# sheet1.net
KiCad netlist of a schematic drawn in Altium Designer
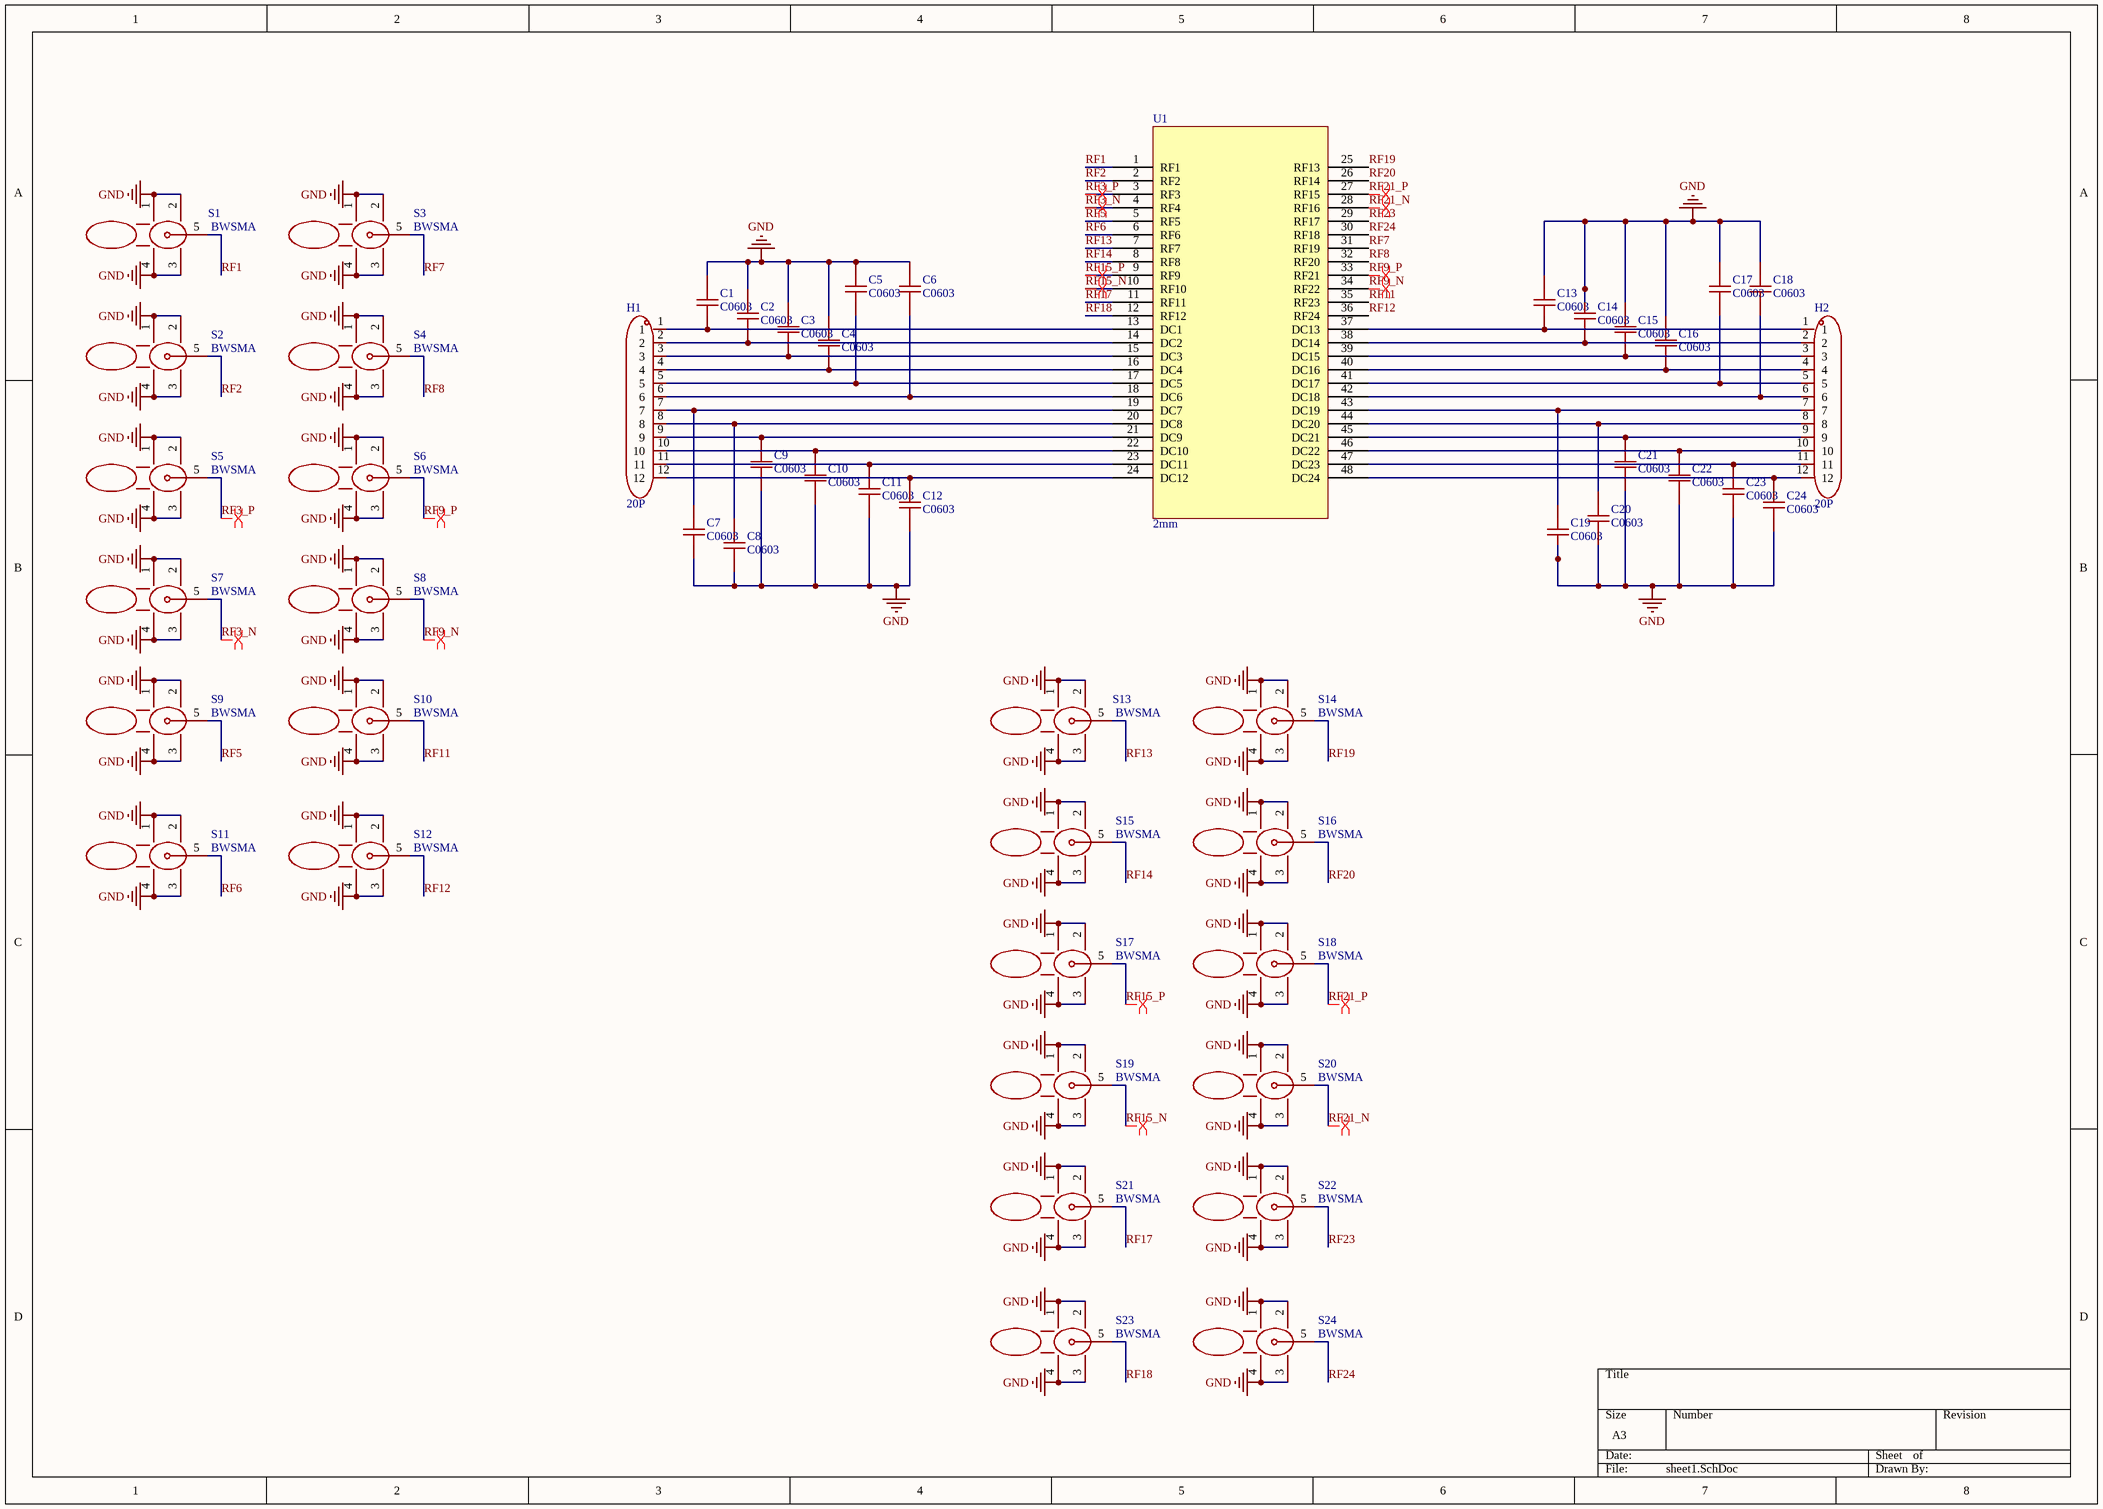
[diagram p0: sheet1.SchDoc]

(export (version "E")
  (design (tool "Eeschema 10.0.6"))
  (components
    (comp (ref "C1") (value "C0603") (footprint "C0603") (libsource (lib "Cap") (part "C0603")))
    (comp (ref "C2") (value "C0603") (footprint "C0603") (libsource (lib "Cap") (part "C0603")))
    (comp (ref "C3") (value "C0603") (footprint "C0603") (libsource (lib "Cap") (part "C0603")))
    (comp (ref "C4") (value "C0603") (footprint "C0603") (libsource (lib "Cap") (part "C0603")))
    (comp (ref "C5") (value "C0603") (footprint "C0603") (libsource (lib "Cap") (part "C0603")))
    (comp (ref "C6") (value "C0603") (footprint "C0603") (libsource (lib "Cap") (part "C0603")))
    (comp (ref "C7") (value "C0603") (footprint "C0603") (libsource (lib "Cap") (part "C0603")))
    (comp (ref "C8") (value "C0603") (footprint "C0603") (libsource (lib "Cap") (part "C0603")))
    (comp (ref "C9") (value "C0603") (footprint "C0603") (libsource (lib "Cap") (part "C0603")))
    (comp (ref "C10") (value "C0603") (footprint "C0603") (libsource (lib "Cap") (part "C0603")))
    (comp (ref "C11") (value "C0603") (footprint "C0603") (libsource (lib "Cap") (part "C0603")))
    (comp (ref "C12") (value "C0603") (footprint "C0603") (libsource (lib "Cap") (part "C0603")))
    (comp (ref "C13") (value "C0603") (footprint "C0603") (libsource (lib "Cap") (part "C0603")))
    (comp (ref "C14") (value "C0603") (footprint "C0603") (libsource (lib "Cap") (part "C0603")))
    (comp (ref "C15") (value "C0603") (footprint "C0603") (libsource (lib "Cap") (part "C0603")))
    (comp (ref "C16") (value "C0603") (footprint "C0603") (libsource (lib "Cap") (part "C0603")))
    (comp (ref "C17") (value "C0603") (footprint "C0603") (libsource (lib "Cap") (part "C0603")))
    (comp (ref "C18") (value "C0603") (footprint "C0603") (libsource (lib "Cap") (part "C0603")))
    (comp (ref "C19") (value "C0603") (footprint "C0603") (libsource (lib "Cap") (part "C0603")))
    (comp (ref "C20") (value "C0603") (footprint "C0603") (libsource (lib "Cap") (part "C0603")))
    (comp (ref "C21") (value "C0603") (footprint "C0603") (libsource (lib "Cap") (part "C0603")))
    (comp (ref "C22") (value "C0603") (footprint "C0603") (libsource (lib "Cap") (part "C0603")))
    (comp (ref "C23") (value "C0603") (footprint "C0603") (libsource (lib "Cap") (part "C0603")))
    (comp (ref "C24") (value "C0603") (footprint "C0603") (libsource (lib "Cap") (part "C0603")))
    (comp (ref "H1") (value "20P") (footprint "20P") (libsource (lib "Header") (part "20P")))
    (comp (ref "H2") (value "20P") (footprint "20P") (libsource (lib "Header") (part "20P")))
    (comp (ref "S1") (value "BWSMA") (footprint "BWSMA") (libsource (lib "SMA") (part "BWSMA")))
    (comp (ref "S2") (value "BWSMA") (footprint "BWSMA") (libsource (lib "SMA") (part "BWSMA")))
    (comp (ref "S3") (value "BWSMA") (footprint "BWSMA") (libsource (lib "SMA") (part "BWSMA")))
    (comp (ref "S4") (value "BWSMA") (footprint "BWSMA") (libsource (lib "SMA") (part "BWSMA")))
    (comp (ref "S5") (value "BWSMA") (footprint "BWSMA") (libsource (lib "SMA") (part "BWSMA")))
    (comp (ref "S6") (value "BWSMA") (footprint "BWSMA") (libsource (lib "SMA") (part "BWSMA")))
    (comp (ref "S7") (value "BWSMA") (footprint "BWSMA") (libsource (lib "SMA") (part "BWSMA")))
    (comp (ref "S8") (value "BWSMA") (footprint "BWSMA") (libsource (lib "SMA") (part "BWSMA")))
    (comp (ref "S9") (value "BWSMA") (footprint "BWSMA") (libsource (lib "SMA") (part "BWSMA")))
    (comp (ref "S10") (value "BWSMA") (footprint "BWSMA") (libsource (lib "SMA") (part "BWSMA")))
    (comp (ref "S11") (value "BWSMA") (footprint "BWSMA") (libsource (lib "SMA") (part "BWSMA")))
    (comp (ref "S12") (value "BWSMA") (footprint "BWSMA") (libsource (lib "SMA") (part "BWSMA")))
    (comp (ref "S13") (value "BWSMA") (footprint "BWSMA") (libsource (lib "SMA") (part "BWSMA")))
    (comp (ref "S14") (value "BWSMA") (footprint "BWSMA") (libsource (lib "SMA") (part "BWSMA")))
    (comp (ref "S15") (value "BWSMA") (footprint "BWSMA") (libsource (lib "SMA") (part "BWSMA")))
    (comp (ref "S16") (value "BWSMA") (footprint "BWSMA") (libsource (lib "SMA") (part "BWSMA")))
    (comp (ref "S17") (value "BWSMA") (footprint "BWSMA") (libsource (lib "SMA") (part "BWSMA")))
    (comp (ref "S18") (value "BWSMA") (footprint "BWSMA") (libsource (lib "SMA") (part "BWSMA")))
    (comp (ref "S19") (value "BWSMA") (footprint "BWSMA") (libsource (lib "SMA") (part "BWSMA")))
    (comp (ref "S20") (value "BWSMA") (footprint "BWSMA") (libsource (lib "SMA") (part "BWSMA")))
    (comp (ref "S21") (value "BWSMA") (footprint "BWSMA") (libsource (lib "SMA") (part "BWSMA")))
    (comp (ref "S22") (value "BWSMA") (footprint "BWSMA") (libsource (lib "SMA") (part "BWSMA")))
    (comp (ref "S23") (value "BWSMA") (footprint "BWSMA") (libsource (lib "SMA") (part "BWSMA")))
    (comp (ref "S24") (value "BWSMA") (footprint "BWSMA") (libsource (lib "SMA") (part "BWSMA")))
    (comp (ref "U1") (value "2mm") (footprint "2mm") (libsource (lib "Chips") (part "2mm")))
  )
  (nets
    (net (code "1") (name "/RF1") (class "Default")
      (node (ref "S1") (pin "5") (pinfunction "5_5") (pintype "passive"))
      (node (ref "U1") (pin "1") (pinfunction "RF1_1") (pintype "passive"))
    )
    (net (code "2") (name "/RF2") (class "Default")
      (node (ref "S2") (pin "5") (pinfunction "5_5") (pintype "passive"))
      (node (ref "U1") (pin "2") (pinfunction "RF2_2") (pintype "passive"))
    )
    (net (code "3") (name "/RF3_N") (class "Default")
      (node (ref "S7") (pin "5") (pinfunction "5_5") (pintype "passive"))
      (node (ref "U1") (pin "4") (pinfunction "RF4_4") (pintype "passive"))
    )
    (net (code "4") (name "/RF3_P") (class "Default")
      (node (ref "S5") (pin "5") (pinfunction "5_5") (pintype "passive"))
      (node (ref "U1") (pin "3") (pinfunction "RF3_3") (pintype "passive"))
    )
    (net (code "5") (name "/RF5") (class "Default")
      (node (ref "S9") (pin "5") (pinfunction "5_5") (pintype "passive"))
      (node (ref "U1") (pin "5") (pinfunction "RF5_5") (pintype "passive"))
    )
    (net (code "6") (name "/RF6") (class "Default")
      (node (ref "S11") (pin "5") (pinfunction "5_5") (pintype "passive"))
      (node (ref "U1") (pin "6") (pinfunction "RF6_6") (pintype "passive"))
    )
    (net (code "7") (name "/RF7") (class "Default")
      (node (ref "S3") (pin "5") (pinfunction "5_5") (pintype "passive"))
      (node (ref "U1") (pin "31") (pinfunction "RF19_31") (pintype "passive"))
    )
    (net (code "8") (name "/RF8") (class "Default")
      (node (ref "S4") (pin "5") (pinfunction "5_5") (pintype "passive"))
      (node (ref "U1") (pin "32") (pinfunction "RF20_32") (pintype "passive"))
    )
    (net (code "9") (name "/RF9_N") (class "Default")
      (node (ref "S8") (pin "5") (pinfunction "5_5") (pintype "passive"))
      (node (ref "U1") (pin "34") (pinfunction "RF22_34") (pintype "passive"))
    )
    (net (code "10") (name "/RF9_P") (class "Default")
      (node (ref "S6") (pin "5") (pinfunction "5_5") (pintype "passive"))
      (node (ref "U1") (pin "33") (pinfunction "RF21_33") (pintype "passive"))
    )
    (net (code "11") (name "/RF11") (class "Default")
      (node (ref "S10") (pin "5") (pinfunction "5_5") (pintype "passive"))
      (node (ref "U1") (pin "35") (pinfunction "RF23_35") (pintype "passive"))
    )
    (net (code "12") (name "/RF12") (class "Default")
      (node (ref "S12") (pin "5") (pinfunction "5_5") (pintype "passive"))
      (node (ref "U1") (pin "36") (pinfunction "RF24_36") (pintype "passive"))
    )
    (net (code "13") (name "/RF13") (class "Default")
      (node (ref "S13") (pin "5") (pinfunction "5_5") (pintype "passive"))
      (node (ref "U1") (pin "7") (pinfunction "RF7_7") (pintype "passive"))
    )
    (net (code "14") (name "/RF14") (class "Default")
      (node (ref "S15") (pin "5") (pinfunction "5_5") (pintype "passive"))
      (node (ref "U1") (pin "8") (pinfunction "RF8_8") (pintype "passive"))
    )
    (net (code "15") (name "/RF15_N") (class "Default")
      (node (ref "S19") (pin "5") (pinfunction "5_5") (pintype "passive"))
      (node (ref "U1") (pin "10") (pinfunction "RF10_10") (pintype "passive"))
    )
    (net (code "16") (name "/RF15_P") (class "Default")
      (node (ref "S17") (pin "5") (pinfunction "5_5") (pintype "passive"))
      (node (ref "U1") (pin "9") (pinfunction "RF9_9") (pintype "passive"))
    )
    (net (code "17") (name "/RF17") (class "Default")
      (node (ref "S21") (pin "5") (pinfunction "5_5") (pintype "passive"))
      (node (ref "U1") (pin "11") (pinfunction "RF11_11") (pintype "passive"))
    )
    (net (code "18") (name "/RF18") (class "Default")
      (node (ref "S23") (pin "5") (pinfunction "5_5") (pintype "passive"))
      (node (ref "U1") (pin "12") (pinfunction "RF12_12") (pintype "passive"))
    )
    (net (code "19") (name "/RF19") (class "Default")
      (node (ref "S14") (pin "5") (pinfunction "5_5") (pintype "passive"))
      (node (ref "U1") (pin "25") (pinfunction "RF13_25") (pintype "passive"))
    )
    (net (code "20") (name "/RF20") (class "Default")
      (node (ref "S16") (pin "5") (pinfunction "5_5") (pintype "passive"))
      (node (ref "U1") (pin "26") (pinfunction "RF14_26") (pintype "passive"))
    )
    (net (code "21") (name "/RF21_N") (class "Default")
      (node (ref "S20") (pin "5") (pinfunction "5_5") (pintype "passive"))
      (node (ref "U1") (pin "28") (pinfunction "RF16_28") (pintype "passive"))
    )
    (net (code "22") (name "/RF21_P") (class "Default")
      (node (ref "S18") (pin "5") (pinfunction "5_5") (pintype "passive"))
      (node (ref "U1") (pin "27") (pinfunction "RF15_27") (pintype "passive"))
    )
    (net (code "23") (name "/RF23") (class "Default")
      (node (ref "S22") (pin "5") (pinfunction "5_5") (pintype "passive"))
      (node (ref "U1") (pin "29") (pinfunction "RF17_29") (pintype "passive"))
    )
    (net (code "24") (name "/RF24") (class "Default")
      (node (ref "S24") (pin "5") (pinfunction "5_5") (pintype "passive"))
      (node (ref "U1") (pin "30") (pinfunction "RF18_30") (pintype "passive"))
    )
    (net (code "25") (name "GND") (class "Default")
      (node (ref "C1") (pin "2") (pinfunction "2_2") (pintype "passive"))
      (node (ref "C10") (pin "1") (pinfunction "1_1") (pintype "passive"))
      (node (ref "C11") (pin "1") (pinfunction "1_1") (pintype "passive"))
      (node (ref "C12") (pin "1") (pinfunction "1_1") (pintype "passive"))
      (node (ref "C13") (pin "2") (pinfunction "2_2") (pintype "passive"))
      (node (ref "C14") (pin "2") (pinfunction "2_2") (pintype "passive"))
      (node (ref "C15") (pin "2") (pinfunction "2_2") (pintype "passive"))
      (node (ref "C16") (pin "2") (pinfunction "2_2") (pintype "passive"))
      (node (ref "C17") (pin "2") (pinfunction "2_2") (pintype "passive"))
      (node (ref "C18") (pin "2") (pinfunction "2_2") (pintype "passive"))
      (node (ref "C19") (pin "1") (pinfunction "1_1") (pintype "passive"))
      (node (ref "C2") (pin "2") (pinfunction "2_2") (pintype "passive"))
      (node (ref "C20") (pin "1") (pinfunction "1_1") (pintype "passive"))
      (node (ref "C21") (pin "1") (pinfunction "1_1") (pintype "passive"))
      (node (ref "C22") (pin "1") (pinfunction "1_1") (pintype "passive"))
      (node (ref "C23") (pin "1") (pinfunction "1_1") (pintype "passive"))
      (node (ref "C24") (pin "1") (pinfunction "1_1") (pintype "passive"))
      (node (ref "C3") (pin "2") (pinfunction "2_2") (pintype "passive"))
      (node (ref "C4") (pin "2") (pinfunction "2_2") (pintype "passive"))
      (node (ref "C5") (pin "2") (pinfunction "2_2") (pintype "passive"))
      (node (ref "C6") (pin "2") (pinfunction "2_2") (pintype "passive"))
      (node (ref "C7") (pin "1") (pinfunction "1_1") (pintype "passive"))
      (node (ref "C8") (pin "1") (pinfunction "1_1") (pintype "passive"))
      (node (ref "C9") (pin "1") (pinfunction "1_1") (pintype "passive"))
      (node (ref "S1") (pin "1") (pinfunction "1_1") (pintype "passive"))
      (node (ref "S1") (pin "2") (pinfunction "2_2") (pintype "passive"))
      (node (ref "S1") (pin "3") (pinfunction "3_3") (pintype "passive"))
      (node (ref "S1") (pin "4") (pinfunction "4_4") (pintype "passive"))
      (node (ref "S10") (pin "1") (pinfunction "1_1") (pintype "passive"))
      (node (ref "S10") (pin "2") (pinfunction "2_2") (pintype "passive"))
      (node (ref "S10") (pin "3") (pinfunction "3_3") (pintype "passive"))
      (node (ref "S10") (pin "4") (pinfunction "4_4") (pintype "passive"))
      (node (ref "S11") (pin "1") (pinfunction "1_1") (pintype "passive"))
      (node (ref "S11") (pin "2") (pinfunction "2_2") (pintype "passive"))
      (node (ref "S11") (pin "3") (pinfunction "3_3") (pintype "passive"))
      (node (ref "S11") (pin "4") (pinfunction "4_4") (pintype "passive"))
      (node (ref "S12") (pin "1") (pinfunction "1_1") (pintype "passive"))
      (node (ref "S12") (pin "2") (pinfunction "2_2") (pintype "passive"))
      (node (ref "S12") (pin "3") (pinfunction "3_3") (pintype "passive"))
      (node (ref "S12") (pin "4") (pinfunction "4_4") (pintype "passive"))
      (node (ref "S13") (pin "1") (pinfunction "1_1") (pintype "passive"))
      (node (ref "S13") (pin "2") (pinfunction "2_2") (pintype "passive"))
      (node (ref "S13") (pin "3") (pinfunction "3_3") (pintype "passive"))
      (node (ref "S13") (pin "4") (pinfunction "4_4") (pintype "passive"))
      (node (ref "S14") (pin "1") (pinfunction "1_1") (pintype "passive"))
      (node (ref "S14") (pin "2") (pinfunction "2_2") (pintype "passive"))
      (node (ref "S14") (pin "3") (pinfunction "3_3") (pintype "passive"))
      (node (ref "S14") (pin "4") (pinfunction "4_4") (pintype "passive"))
      (node (ref "S15") (pin "1") (pinfunction "1_1") (pintype "passive"))
      (node (ref "S15") (pin "2") (pinfunction "2_2") (pintype "passive"))
      (node (ref "S15") (pin "3") (pinfunction "3_3") (pintype "passive"))
      (node (ref "S15") (pin "4") (pinfunction "4_4") (pintype "passive"))
      (node (ref "S16") (pin "1") (pinfunction "1_1") (pintype "passive"))
      (node (ref "S16") (pin "2") (pinfunction "2_2") (pintype "passive"))
      (node (ref "S16") (pin "3") (pinfunction "3_3") (pintype "passive"))
      (node (ref "S16") (pin "4") (pinfunction "4_4") (pintype "passive"))
      (node (ref "S17") (pin "1") (pinfunction "1_1") (pintype "passive"))
      (node (ref "S17") (pin "2") (pinfunction "2_2") (pintype "passive"))
      (node (ref "S17") (pin "3") (pinfunction "3_3") (pintype "passive"))
      (node (ref "S17") (pin "4") (pinfunction "4_4") (pintype "passive"))
      (node (ref "S18") (pin "1") (pinfunction "1_1") (pintype "passive"))
      (node (ref "S18") (pin "2") (pinfunction "2_2") (pintype "passive"))
      (node (ref "S18") (pin "3") (pinfunction "3_3") (pintype "passive"))
      (node (ref "S18") (pin "4") (pinfunction "4_4") (pintype "passive"))
      (node (ref "S19") (pin "1") (pinfunction "1_1") (pintype "passive"))
      (node (ref "S19") (pin "2") (pinfunction "2_2") (pintype "passive"))
      (node (ref "S19") (pin "3") (pinfunction "3_3") (pintype "passive"))
      (node (ref "S19") (pin "4") (pinfunction "4_4") (pintype "passive"))
      (node (ref "S2") (pin "1") (pinfunction "1_1") (pintype "passive"))
      (node (ref "S2") (pin "2") (pinfunction "2_2") (pintype "passive"))
      (node (ref "S2") (pin "3") (pinfunction "3_3") (pintype "passive"))
      (node (ref "S2") (pin "4") (pinfunction "4_4") (pintype "passive"))
      (node (ref "S20") (pin "1") (pinfunction "1_1") (pintype "passive"))
      (node (ref "S20") (pin "2") (pinfunction "2_2") (pintype "passive"))
      (node (ref "S20") (pin "3") (pinfunction "3_3") (pintype "passive"))
      (node (ref "S20") (pin "4") (pinfunction "4_4") (pintype "passive"))
      (node (ref "S21") (pin "1") (pinfunction "1_1") (pintype "passive"))
      (node (ref "S21") (pin "2") (pinfunction "2_2") (pintype "passive"))
      (node (ref "S21") (pin "3") (pinfunction "3_3") (pintype "passive"))
      (node (ref "S21") (pin "4") (pinfunction "4_4") (pintype "passive"))
      (node (ref "S22") (pin "1") (pinfunction "1_1") (pintype "passive"))
      (node (ref "S22") (pin "2") (pinfunction "2_2") (pintype "passive"))
      (node (ref "S22") (pin "3") (pinfunction "3_3") (pintype "passive"))
      (node (ref "S22") (pin "4") (pinfunction "4_4") (pintype "passive"))
      (node (ref "S23") (pin "1") (pinfunction "1_1") (pintype "passive"))
      (node (ref "S23") (pin "2") (pinfunction "2_2") (pintype "passive"))
      (node (ref "S23") (pin "3") (pinfunction "3_3") (pintype "passive"))
      (node (ref "S23") (pin "4") (pinfunction "4_4") (pintype "passive"))
      (node (ref "S24") (pin "1") (pinfunction "1_1") (pintype "passive"))
      (node (ref "S24") (pin "2") (pinfunction "2_2") (pintype "passive"))
      (node (ref "S24") (pin "3") (pinfunction "3_3") (pintype "passive"))
      (node (ref "S24") (pin "4") (pinfunction "4_4") (pintype "passive"))
      (node (ref "S3") (pin "1") (pinfunction "1_1") (pintype "passive"))
      (node (ref "S3") (pin "2") (pinfunction "2_2") (pintype "passive"))
      (node (ref "S3") (pin "3") (pinfunction "3_3") (pintype "passive"))
      (node (ref "S3") (pin "4") (pinfunction "4_4") (pintype "passive"))
      (node (ref "S4") (pin "1") (pinfunction "1_1") (pintype "passive"))
      (node (ref "S4") (pin "2") (pinfunction "2_2") (pintype "passive"))
      (node (ref "S4") (pin "3") (pinfunction "3_3") (pintype "passive"))
      (node (ref "S4") (pin "4") (pinfunction "4_4") (pintype "passive"))
      (node (ref "S5") (pin "1") (pinfunction "1_1") (pintype "passive"))
      (node (ref "S5") (pin "2") (pinfunction "2_2") (pintype "passive"))
      (node (ref "S5") (pin "3") (pinfunction "3_3") (pintype "passive"))
      (node (ref "S5") (pin "4") (pinfunction "4_4") (pintype "passive"))
      (node (ref "S6") (pin "1") (pinfunction "1_1") (pintype "passive"))
      (node (ref "S6") (pin "2") (pinfunction "2_2") (pintype "passive"))
      (node (ref "S6") (pin "3") (pinfunction "3_3") (pintype "passive"))
      (node (ref "S6") (pin "4") (pinfunction "4_4") (pintype "passive"))
      (node (ref "S7") (pin "1") (pinfunction "1_1") (pintype "passive"))
      (node (ref "S7") (pin "2") (pinfunction "2_2") (pintype "passive"))
      (node (ref "S7") (pin "3") (pinfunction "3_3") (pintype "passive"))
      (node (ref "S7") (pin "4") (pinfunction "4_4") (pintype "passive"))
      (node (ref "S8") (pin "1") (pinfunction "1_1") (pintype "passive"))
      (node (ref "S8") (pin "2") (pinfunction "2_2") (pintype "passive"))
      (node (ref "S8") (pin "3") (pinfunction "3_3") (pintype "passive"))
      (node (ref "S8") (pin "4") (pinfunction "4_4") (pintype "passive"))
      (node (ref "S9") (pin "1") (pinfunction "1_1") (pintype "passive"))
      (node (ref "S9") (pin "2") (pinfunction "2_2") (pintype "passive"))
      (node (ref "S9") (pin "3") (pinfunction "3_3") (pintype "passive"))
      (node (ref "S9") (pin "4") (pinfunction "4_4") (pintype "passive"))
    )
    (net (code "26") (name "Net-(U1-DC1)") (class "Default")
      (node (ref "C1") (pin "1") (pinfunction "1_1") (pintype "passive"))
      (node (ref "H1") (pin "1") (pinfunction "1_1") (pintype "passive"))
      (node (ref "U1") (pin "13") (pinfunction "DC1_13") (pintype "passive"))
    )
    (net (code "27") (name "Net-(U1-DC2)") (class "Default")
      (node (ref "C2") (pin "1") (pinfunction "1_1") (pintype "passive"))
      (node (ref "H1") (pin "2") (pinfunction "2_2") (pintype "passive"))
      (node (ref "U1") (pin "14") (pinfunction "DC2_14") (pintype "passive"))
    )
    (net (code "28") (name "Net-(U1-DC3)") (class "Default")
      (node (ref "C3") (pin "1") (pinfunction "1_1") (pintype "passive"))
      (node (ref "H1") (pin "3") (pinfunction "3_3") (pintype "passive"))
      (node (ref "U1") (pin "15") (pinfunction "DC3_15") (pintype "passive"))
    )
    (net (code "29") (name "Net-(U1-DC4)") (class "Default")
      (node (ref "C4") (pin "1") (pinfunction "1_1") (pintype "passive"))
      (node (ref "H1") (pin "4") (pinfunction "4_4") (pintype "passive"))
      (node (ref "U1") (pin "16") (pinfunction "DC4_16") (pintype "passive"))
    )
    (net (code "30") (name "Net-(U1-DC5)") (class "Default")
      (node (ref "C5") (pin "1") (pinfunction "1_1") (pintype "passive"))
      (node (ref "H1") (pin "5") (pinfunction "5_5") (pintype "passive"))
      (node (ref "U1") (pin "17") (pinfunction "DC5_17") (pintype "passive"))
    )
    (net (code "31") (name "Net-(U1-DC6)") (class "Default")
      (node (ref "C6") (pin "1") (pinfunction "1_1") (pintype "passive"))
      (node (ref "H1") (pin "6") (pinfunction "6_6") (pintype "passive"))
      (node (ref "U1") (pin "18") (pinfunction "DC6_18") (pintype "passive"))
    )
    (net (code "32") (name "Net-(U1-DC7)") (class "Default")
      (node (ref "C7") (pin "2") (pinfunction "2_2") (pintype "passive"))
      (node (ref "H1") (pin "7") (pinfunction "7_7") (pintype "passive"))
      (node (ref "U1") (pin "19") (pinfunction "DC7_19") (pintype "passive"))
    )
    (net (code "33") (name "Net-(U1-DC8)") (class "Default")
      (node (ref "C8") (pin "2") (pinfunction "2_2") (pintype "passive"))
      (node (ref "H1") (pin "8") (pinfunction "8_8") (pintype "passive"))
      (node (ref "U1") (pin "20") (pinfunction "DC8_20") (pintype "passive"))
    )
    (net (code "34") (name "Net-(U1-DC9)") (class "Default")
      (node (ref "C9") (pin "2") (pinfunction "2_2") (pintype "passive"))
      (node (ref "H1") (pin "9") (pinfunction "9_9") (pintype "passive"))
      (node (ref "U1") (pin "21") (pinfunction "DC9_21") (pintype "passive"))
    )
    (net (code "35") (name "Net-(U1-DC10)") (class "Default")
      (node (ref "C10") (pin "2") (pinfunction "2_2") (pintype "passive"))
      (node (ref "H1") (pin "10") (pinfunction "10_10") (pintype "passive"))
      (node (ref "U1") (pin "22") (pinfunction "DC10_22") (pintype "passive"))
    )
    (net (code "36") (name "Net-(U1-DC11)") (class "Default")
      (node (ref "C11") (pin "2") (pinfunction "2_2") (pintype "passive"))
      (node (ref "H1") (pin "11") (pinfunction "11_11") (pintype "passive"))
      (node (ref "U1") (pin "23") (pinfunction "DC11_23") (pintype "passive"))
    )
    (net (code "37") (name "Net-(U1-DC12)") (class "Default")
      (node (ref "C12") (pin "2") (pinfunction "2_2") (pintype "passive"))
      (node (ref "H1") (pin "12") (pinfunction "12_12") (pintype "passive"))
      (node (ref "U1") (pin "24") (pinfunction "DC12_24") (pintype "passive"))
    )
    (net (code "38") (name "Net-(U1-DC13)") (class "Default")
      (node (ref "C13") (pin "1") (pinfunction "1_1") (pintype "passive"))
      (node (ref "H2") (pin "1") (pinfunction "1_1") (pintype "passive"))
      (node (ref "U1") (pin "37") (pinfunction "DC13_37") (pintype "passive"))
    )
    (net (code "39") (name "Net-(U1-DC14)") (class "Default")
      (node (ref "C14") (pin "1") (pinfunction "1_1") (pintype "passive"))
      (node (ref "H2") (pin "2") (pinfunction "2_2") (pintype "passive"))
      (node (ref "U1") (pin "38") (pinfunction "DC14_38") (pintype "passive"))
    )
    (net (code "40") (name "Net-(U1-DC15)") (class "Default")
      (node (ref "C15") (pin "1") (pinfunction "1_1") (pintype "passive"))
      (node (ref "H2") (pin "3") (pinfunction "3_3") (pintype "passive"))
      (node (ref "U1") (pin "39") (pinfunction "DC15_39") (pintype "passive"))
    )
    (net (code "41") (name "Net-(U1-DC16)") (class "Default")
      (node (ref "C16") (pin "1") (pinfunction "1_1") (pintype "passive"))
      (node (ref "H2") (pin "4") (pinfunction "4_4") (pintype "passive"))
      (node (ref "U1") (pin "40") (pinfunction "DC16_40") (pintype "passive"))
    )
    (net (code "42") (name "Net-(U1-DC17)") (class "Default")
      (node (ref "C17") (pin "1") (pinfunction "1_1") (pintype "passive"))
      (node (ref "H2") (pin "5") (pinfunction "5_5") (pintype "passive"))
      (node (ref "U1") (pin "41") (pinfunction "DC17_41") (pintype "passive"))
    )
    (net (code "43") (name "Net-(U1-DC18)") (class "Default")
      (node (ref "C18") (pin "1") (pinfunction "1_1") (pintype "passive"))
      (node (ref "H2") (pin "6") (pinfunction "6_6") (pintype "passive"))
      (node (ref "U1") (pin "42") (pinfunction "DC18_42") (pintype "passive"))
    )
    (net (code "44") (name "Net-(U1-DC19)") (class "Default")
      (node (ref "C19") (pin "2") (pinfunction "2_2") (pintype "passive"))
      (node (ref "H2") (pin "7") (pinfunction "7_7") (pintype "passive"))
      (node (ref "U1") (pin "43") (pinfunction "DC19_43") (pintype "passive"))
    )
    (net (code "45") (name "Net-(U1-DC20)") (class "Default")
      (node (ref "C20") (pin "2") (pinfunction "2_2") (pintype "passive"))
      (node (ref "H2") (pin "8") (pinfunction "8_8") (pintype "passive"))
      (node (ref "U1") (pin "44") (pinfunction "DC20_44") (pintype "passive"))
    )
    (net (code "46") (name "Net-(U1-DC21)") (class "Default")
      (node (ref "C21") (pin "2") (pinfunction "2_2") (pintype "passive"))
      (node (ref "H2") (pin "9") (pinfunction "9_9") (pintype "passive"))
      (node (ref "U1") (pin "45") (pinfunction "DC21_45") (pintype "passive"))
    )
    (net (code "47") (name "Net-(U1-DC22)") (class "Default")
      (node (ref "C22") (pin "2") (pinfunction "2_2") (pintype "passive"))
      (node (ref "H2") (pin "10") (pinfunction "10_10") (pintype "passive"))
      (node (ref "U1") (pin "46") (pinfunction "DC22_46") (pintype "passive"))
    )
    (net (code "48") (name "Net-(U1-DC23)") (class "Default")
      (node (ref "C23") (pin "2") (pinfunction "2_2") (pintype "passive"))
      (node (ref "H2") (pin "11") (pinfunction "11_11") (pintype "passive"))
      (node (ref "U1") (pin "47") (pinfunction "DC23_47") (pintype "passive"))
    )
    (net (code "49") (name "Net-(U1-DC24)") (class "Default")
      (node (ref "C24") (pin "2") (pinfunction "2_2") (pintype "passive"))
      (node (ref "H2") (pin "12") (pinfunction "12_12") (pintype "passive"))
      (node (ref "U1") (pin "48") (pinfunction "DC24_48") (pintype "passive"))
    )
  )
)
